# LM2596.net
KiCad netlist of a schematic drawn in Altium Designer
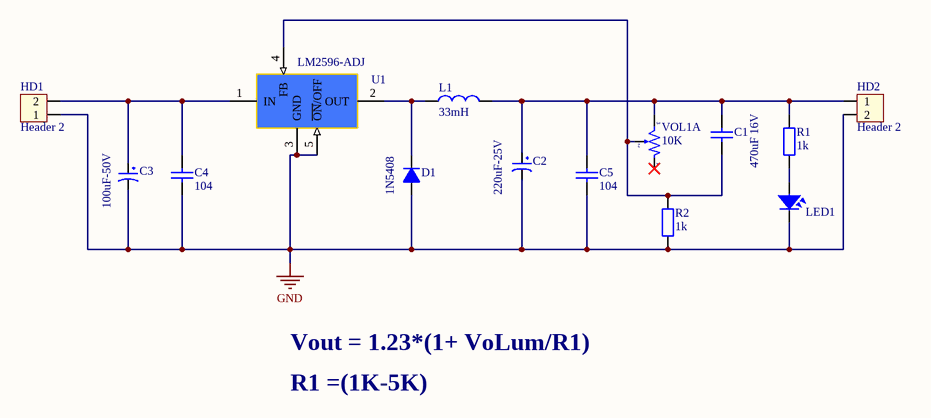
[diagram p0: LM2596.SchDoc]

(export (version "E")
  (design (tool "Eeschema 10.0.6"))
  (components
    (comp (ref "C1")
      (value "470uF 16V")
      (footprint "tu gom")
      (description "Cắm")
      (libsource (lib "NhomLib") (part "Tu gom 100 50V"))
    )
    (comp (ref "C2")
      (value "220uF-25V")
      (footprint "Tu hoa 8mm")
      (description "Cắm")
      (libsource (lib "NhomLib") (part "Tu Hoa 220uF 25V 8x10"))
    )
    (comp (ref "C3")
      (value "100uF-50V")
      (footprint "tu hoa 8mm")
      (description "Cắm")
      (libsource (lib "NhomLib") (part "Tu Hoa 100uF 50V 8x11"))
    )
    (comp (ref "C4")
      (value "104")
      (footprint "tu gom")
      (description "Cắm")
      (libsource (lib "NhomLib") (part "Tu gom 100 50V"))
    )
    (comp (ref "C5")
      (value "104")
      (footprint "tu gom")
      (description "Cắm")
      (libsource (lib "NhomLib") (part "Tu gom 100 50V"))
    )
    (comp (ref "D1")
      (value "1N5408")
      (footprint "D5A")
      (description "Diode 5A")
      (libsource (lib "syhaunguyen") (part "D5A"))
    )
    (comp (ref "HD1")
      (value "Header 2")
      (footprint "HED2")
      (description "Header 2 (Green)")
      (libsource (lib "") (part "Hed2_1"))
    )
    (comp (ref "HD2")
      (value "Header 2")
      (footprint "HED2")
      (description "Header 2 (Green)")
      (libsource (lib "NhomLib") (part "Hed2"))
    )
    (comp (ref "L1")
      (value "33mH")
      (footprint "R1/4W")
      (description "Cắm")
      (libsource (lib "NhomLib") (part "Cuon cam 220uH"))
    )
    (comp (ref "LED1")
      (value "LED")
      (footprint "LED-5-RED")
      (description "LED Single colour Green and Red")
      (libsource (lib "syhaunguyen") (part "LED"))
    )
    (comp (ref "R1")
      (value "1k")
      (footprint "R1/4W")
      (description "Resistor 1/4W")
      (libsource (lib "syhaunguyen") (part "R1/4W"))
    )
    (comp (ref "R2")
      (value "1k")
      (footprint "R1/4W")
      (description "Resistor 1/4W")
      (libsource (lib "syhaunguyen") (part "R1/4W"))
    )
    (comp (ref "U1")
      (value "LM2596-ADJ")
      (footprint "D2-PACK5")
      (description "Simple Switcher 3A Step Down Voltage Regulator")
      (fields (field (name "PUBLISHER") "Altium Limited"))
      (libsource (lib "VPMyLibrary") (part "LM2596"))
    )
    (comp (ref "VOL1")
      (value "10K")
      (footprint "VR1")
      (description "Volume control Dual")
      (libsource (lib "SCH Chuan") (part "VOL-D"))
    )
  )
  (nets
    (net (code "1") (name "GND") (class "Default")
      (node (ref "C2") (pin "2") (pinfunction "2_2") (pintype "passive"))
      (node (ref "C3") (pin "2") (pinfunction "2_2") (pintype "passive"))
      (node (ref "C4") (pin "2") (pinfunction "2_2") (pintype "passive"))
      (node (ref "C5") (pin "2") (pinfunction "2_2") (pintype "passive"))
      (node (ref "D1") (pin "1") (pinfunction "A_1") (pintype "passive"))
      (node (ref "HD1") (pin "1") (pinfunction "1_1") (pintype "passive"))
      (node (ref "HD2") (pin "2") (pinfunction "2_2") (pintype "passive"))
      (node (ref "LED1") (pin "2") (pinfunction "2_2") (pintype "passive"))
      (node (ref "R2") (pin "1") (pinfunction "1_1") (pintype "passive"))
      (node (ref "U1") (pin "3") (pinfunction "GND_3") (pintype "power_in"))
      (node (ref "U1") (pin "5") (pinfunction "~{ON}/OFF_5") (pintype "input"))
    )
    (net (code "2") (name "Net-(C1-Pad1)") (class "Default")
      (node (ref "C1") (pin "1") (pinfunction "1_1") (pintype "passive"))
      (node (ref "C2") (pin "1") (pinfunction "1_1") (pintype "passive"))
      (node (ref "C5") (pin "1") (pinfunction "1_1") (pintype "passive"))
      (node (ref "HD2") (pin "1") (pinfunction "1_1") (pintype "passive"))
      (node (ref "L1") (pin "2") (pinfunction "2_2") (pintype "passive"))
      (node (ref "R1") (pin "2") (pinfunction "2_2") (pintype "passive"))
      (node (ref "VOL1") (pin "3") (pinfunction "3_3") (pintype "passive"))
    )
    (net (code "3") (name "Net-(D1-K)") (class "Default")
      (node (ref "D1") (pin "2") (pinfunction "K_2") (pintype "passive"))
      (node (ref "L1") (pin "1") (pinfunction "1_1") (pintype "passive"))
      (node (ref "U1") (pin "2") (pinfunction "OUT_2") (pintype "power_in"))
    )
    (net (code "4") (name "Net-(LED1-Pad1)") (class "Default")
      (node (ref "LED1") (pin "1") (pinfunction "1_1") (pintype "passive"))
      (node (ref "R1") (pin "1") (pinfunction "1_1") (pintype "passive"))
    )
    (net (code "5") (name "Net-(U1-FB)") (class "Default")
      (node (ref "C1") (pin "2") (pinfunction "2_2") (pintype "passive"))
      (node (ref "R2") (pin "2") (pinfunction "2_2") (pintype "passive"))
      (node (ref "U1") (pin "4") (pinfunction "FB_4") (pintype "input"))
      (node (ref "VOL1") (pin "2") (pinfunction "2_2") (pintype "passive"))
    )
    (net (code "6") (name "Net-(U1-IN)") (class "Default")
      (node (ref "C3") (pin "1") (pinfunction "1_1") (pintype "passive"))
      (node (ref "C4") (pin "1") (pinfunction "1_1") (pintype "passive"))
      (node (ref "HD1") (pin "2") (pinfunction "2_2") (pintype "passive"))
      (node (ref "U1") (pin "1") (pinfunction "IN_1") (pintype "power_in"))
    )
    (net (code "7") (name "unconnected-(VOL1-Pad1)") (class "Default")
      (node (ref "VOL1") (pin "1") (pinfunction "1_1") (pintype "passive+no_connect"))
    )
  )
)
